# Ethernet_v2.net
KiCad netlist of a schematic drawn in Altium Designer
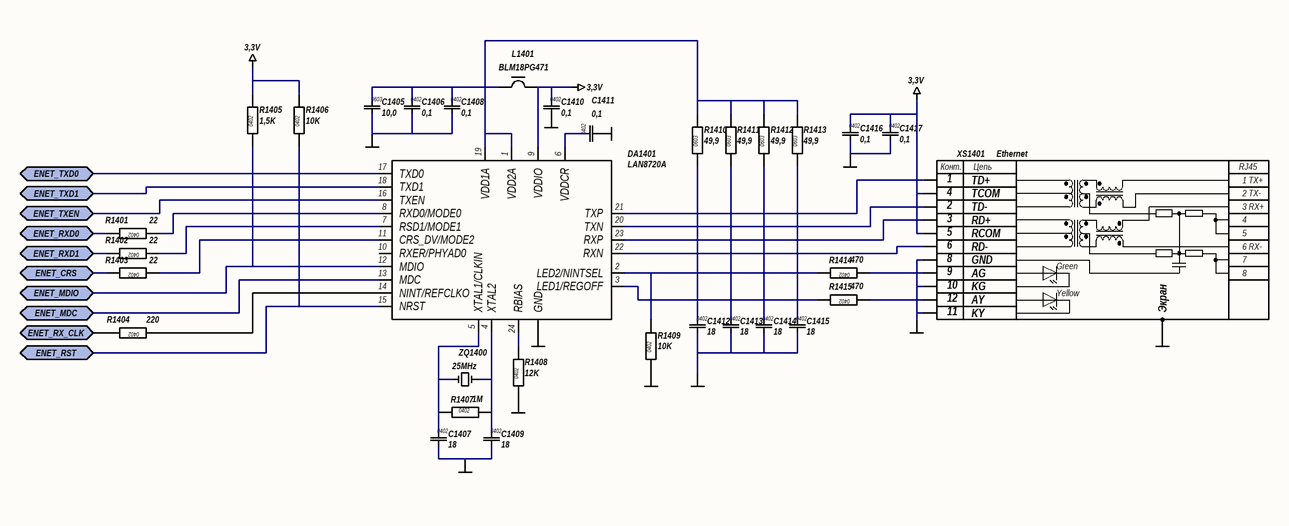
[diagram p0: Ethernet v2.SchDoc]

(export (version "E")
  (design (tool "Eeschema 10.0.6"))
  (components
    (comp (ref "C1405")
      (value "10,0")
      (footprint "CAP0603")
      (description "Конденсатор чип")
      (libsource (lib "EwgPassive") (part "CAP_0603"))
    )
    (comp (ref "C1406")
      (value "0,1")
      (footprint "CAP0402")
      (description "Конденсатор чип")
      (libsource (lib "EwgPassive") (part "CAP_0402"))
    )
    (comp (ref "C1407")
      (value "18")
      (footprint "CAP0402")
      (description "Конденсатор чип")
      (libsource (lib "EwgPassive") (part "CAP_0402"))
    )
    (comp (ref "C1408")
      (value "0,1")
      (footprint "CAP0402")
      (description "Конденсатор чип")
      (libsource (lib "EwgPassive") (part "CAP_0402"))
    )
    (comp (ref "C1409")
      (value "18")
      (footprint "CAP0402")
      (description "Конденсатор чип")
      (libsource (lib "EwgPassive") (part "CAP_0402"))
    )
    (comp (ref "C1410")
      (value "0,1")
      (footprint "CAP0402")
      (description "Конденсатор чип")
      (libsource (lib "EwgPassive") (part "CAP_0402"))
    )
    (comp (ref "C1411")
      (value "0,1")
      (footprint "CAP0402")
      (description "Конденсатор чип")
      (libsource (lib "EwgPassive") (part "CAP_0402"))
    )
    (comp (ref "C1412")
      (value "18")
      (footprint "CAP0402")
      (description "Конденсатор чип")
      (libsource (lib "EwgPassive") (part "CAP_0402"))
    )
    (comp (ref "C1413")
      (value "18")
      (footprint "CAP0402")
      (description "Конденсатор чип")
      (libsource (lib "EwgPassive") (part "CAP_0402"))
    )
    (comp (ref "C1414")
      (value "18")
      (footprint "CAP0402")
      (description "Конденсатор чип")
      (libsource (lib "EwgPassive") (part "CAP_0402"))
    )
    (comp (ref "C1415")
      (value "18")
      (footprint "CAP0402")
      (description "Конденсатор чип")
      (libsource (lib "EwgPassive") (part "CAP_0402"))
    )
    (comp (ref "C1416")
      (value "0,1")
      (footprint "CAP0402")
      (description "Конденсатор чип")
      (libsource (lib "EwgPassive") (part "CAP_0402"))
    )
    (comp (ref "C1417")
      (value "0,1")
      (footprint "CAP0402")
      (description "Конденсатор чип")
      (libsource (lib "EwgPassive") (part "CAP_0402"))
    )
    (comp (ref "DA1401")
      (value "LAN8720A")
      (footprint "LAN8720")
      (description "Интерфейс Ethernet")
      (libsource (lib "EwgMicrochips") (part "LAN8720A"))
    )
    (comp (ref "L1401")
      (value "BLM18PG471")
      (footprint "FB0603")
      (description "Ферритовая бусина")
      (libsource (lib "EwgPassive") (part "BLM18PG"))
    )
    (comp (ref "R1401")
      (value "22")
      (footprint "RES0402")
      (description "Резистор чип")
      (libsource (lib "EwgPassive") (part "RES_0402"))
    )
    (comp (ref "R1402")
      (value "22")
      (footprint "RES0402")
      (description "Резистор чип")
      (libsource (lib "EwgPassive") (part "RES_0402"))
    )
    (comp (ref "R1403")
      (value "22")
      (footprint "RES0402")
      (description "Резистор чип")
      (libsource (lib "EwgPassive") (part "RES_0402"))
    )
    (comp (ref "R1404")
      (value "220")
      (footprint "RES0402")
      (description "Резистор чип")
      (libsource (lib "EwgPassive") (part "RES_0402"))
    )
    (comp (ref "R1405")
      (value "1,5K")
      (footprint "RES0402")
      (description "Резистор чип")
      (libsource (lib "EwgPassive") (part "RES_0402"))
    )
    (comp (ref "R1406")
      (value "10K")
      (footprint "RES0402")
      (description "Резистор чип")
      (libsource (lib "EwgPassive") (part "RES_0402"))
    )
    (comp (ref "R1407")
      (value "1M")
      (footprint "RES0402")
      (description "Резистор чип")
      (libsource (lib "EwgPassive") (part "RES_0402"))
    )
    (comp (ref "R1408")
      (value "12K")
      (footprint "RES0402")
      (description "Резистор чип")
      (libsource (lib "") (part "RES_0402_1"))
    )
    (comp (ref "R1409")
      (value "10K")
      (footprint "RES0402")
      (description "Резистор чип")
      (libsource (lib "") (part "RES_0402_1"))
    )
    (comp (ref "R1410")
      (value "49,9")
      (footprint "RES0603")
      (description "Резистор чип")
      (libsource (lib "EwgPassive") (part "RES_0603"))
    )
    (comp (ref "R1411")
      (value "49,9")
      (footprint "RES0603")
      (description "Резистор чип")
      (libsource (lib "EwgPassive") (part "RES_0603"))
    )
    (comp (ref "R1412")
      (value "49,9")
      (footprint "RES0603")
      (description "Резистор чип")
      (libsource (lib "EwgPassive") (part "RES_0603"))
    )
    (comp (ref "R1413")
      (value "49,9")
      (footprint "RES0603")
      (description "Резистор чип")
      (libsource (lib "EwgPassive") (part "RES_0603"))
    )
    (comp (ref "R1414")
      (value "470")
      (footprint "RES0402")
      (description "Резистор чип")
      (libsource (lib "EwgPassive") (part "RES_0402"))
    )
    (comp (ref "R1415")
      (value "470")
      (footprint "RES0402")
      (description "Резистор чип")
      (libsource (lib "EwgPassive") (part "RES_0402"))
    )
    (comp (ref "XS1401")
      (value "Ethernet")
      (footprint "HR911105A")
      (description "Разъем RJ45 с трансформатором и LED")
      (libsource (lib "EwgConnectors") (part "RJ45-HR911105A"))
    )
    (comp (ref "ZQ1400")
      (value "25MHz")
      (footprint "KX-7")
      (description "Кварц")
      (libsource (lib "EwgPassive") (part "KX-7"))
    )
  )
  (nets
    (net (code "1") (name "/ENET_CRS") (class "Default") (node (ref "R1403") (pin "2") (pintype "passive")))
    (net (code "2") (name "/ENET_MDC") (class "Default")
      (node (ref "DA1401") (pin "13") (pinfunction "MDC_13") (pintype "passive"))
    )
    (net (code "3") (name "/ENET_MDIO") (class "Default")
      (node (ref "DA1401") (pin "12") (pinfunction "MDIO_12") (pintype "passive"))
      (node (ref "R1405") (pin "1") (pintype "passive"))
    )
    (net (code "4") (name "/ENET_RST") (class "Default")
      (node (ref "DA1401") (pin "15") (pinfunction "NRST_15") (pintype "passive"))
      (node (ref "R1406") (pin "1") (pintype "passive"))
    )
    (net (code "5") (name "/ENET_RXD0") (class "Default") (node (ref "R1401") (pin "2") (pintype "passive")))
    (net (code "6") (name "/ENET_RXD1") (class "Default") (node (ref "R1402") (pin "2") (pintype "passive")))
    (net (code "7") (name "/ENET_RX_CLK") (class "Default")
      (node (ref "R1404") (pin "2") (pintype "passive"))
    )
    (net (code "8") (name "/ENET_TXD0") (class "Default")
      (node (ref "DA1401") (pin "17") (pinfunction "TXD0_17") (pintype "passive"))
    )
    (net (code "9") (name "/ENET_TXD1") (class "Default")
      (node (ref "DA1401") (pin "18") (pinfunction "TXD1_18") (pintype "passive"))
    )
    (net (code "10") (name "/ENET_TXEN") (class "Default")
      (node (ref "DA1401") (pin "16") (pinfunction "TXEN_16") (pintype "passive"))
    )
    (net (code "11") (name "3,3V") (class "Default")
      (node (ref "C1410") (pin "1") (pintype "passive"))
      (node (ref "C1416") (pin "1") (pintype "passive"))
      (node (ref "C1417") (pin "1") (pintype "passive"))
      (node (ref "DA1401") (pin "9") (pinfunction "VDDIO_9") (pintype "passive"))
      (node (ref "L1401") (pin "2") (pintype "passive"))
      (node (ref "R1405") (pin "2") (pintype "passive"))
      (node (ref "R1406") (pin "2") (pintype "passive"))
      (node (ref "XS1401") (pin "4") (pinfunction "TCOM_4") (pintype "passive"))
      (node (ref "XS1401") (pin "5") (pinfunction "RCOM_5") (pintype "passive"))
    )
    (net (code "12") (name "GND") (class "Default")
      (node (ref "C1405") (pin "2") (pintype "passive"))
      (node (ref "C1406") (pin "2") (pintype "passive"))
      (node (ref "C1407") (pin "2") (pintype "passive"))
      (node (ref "C1408") (pin "2") (pintype "passive"))
      (node (ref "C1409") (pin "2") (pintype "passive"))
      (node (ref "C1410") (pin "2") (pintype "passive"))
      (node (ref "C1411") (pin "2") (pintype "passive"))
      (node (ref "C1412") (pin "2") (pintype "passive"))
      (node (ref "C1413") (pin "2") (pintype "passive"))
      (node (ref "C1414") (pin "2") (pintype "passive"))
      (node (ref "C1415") (pin "2") (pintype "passive"))
      (node (ref "C1416") (pin "2") (pintype "passive"))
      (node (ref "C1417") (pin "2") (pintype "passive"))
      (node (ref "DA1401") (pin "0") (pinfunction "GND_0") (pintype "passive"))
      (node (ref "R1408") (pin "1") (pintype "passive"))
      (node (ref "R1409") (pin "1") (pintype "passive"))
      (node (ref "XS1401") (pin "0") (pinfunction "Экран_0") (pintype "passive"))
      (node (ref "XS1401") (pin "10") (pinfunction "KG_10") (pintype "passive"))
      (node (ref "XS1401") (pin "11") (pinfunction "KY_11") (pintype "passive"))
      (node (ref "XS1401") (pin "8") (pinfunction "GND_8") (pintype "passive"))
    )
    (net (code "13") (name "Net-(DA1401-CRS_DV{slash}MODE2)") (class "Default")
      (node (ref "DA1401") (pin "11") (pinfunction "CRS_DV/MODE2_11") (pintype "passive"))
      (node (ref "R1403") (pin "1") (pintype "passive"))
    )
    (net (code "14") (name "Net-(DA1401-LED1{slash}REGOFF)") (class "Default")
      (node (ref "DA1401") (pin "3") (pinfunction "LED1/REGOFF_3") (pintype "passive"))
      (node (ref "R1415") (pin "2") (pintype "passive"))
    )
    (net (code "15") (name "Net-(DA1401-LED2{slash}NINTSEL)") (class "Default")
      (node (ref "DA1401") (pin "2") (pinfunction "LED2/NINTSEL_2") (pintype "passive"))
      (node (ref "R1409") (pin "2") (pintype "passive"))
      (node (ref "R1414") (pin "2") (pintype "passive"))
    )
    (net (code "16") (name "Net-(DA1401-NINT{slash}REFCLKO)") (class "Default")
      (node (ref "DA1401") (pin "14") (pinfunction "NINT/REFCLKO_14") (pintype "passive"))
      (node (ref "R1404") (pin "1") (pintype "passive"))
    )
    (net (code "17") (name "Net-(DA1401-RBIAS)") (class "Default")
      (node (ref "DA1401") (pin "24") (pinfunction "RBIAS_24") (pintype "passive"))
      (node (ref "R1408") (pin "2") (pintype "passive"))
    )
    (net (code "18") (name "Net-(DA1401-RSD1{slash}MODE1)") (class "Default")
      (node (ref "DA1401") (pin "7") (pinfunction "RSD1/MODE1_7") (pintype "passive"))
      (node (ref "R1402") (pin "1") (pintype "passive"))
    )
    (net (code "19") (name "Net-(DA1401-RXD0{slash}MODE0)") (class "Default")
      (node (ref "DA1401") (pin "8") (pinfunction "RXD0/MODE0_8") (pintype "passive"))
      (node (ref "R1401") (pin "1") (pintype "passive"))
    )
    (net (code "20") (name "Net-(DA1401-RXN)") (class "Default")
      (node (ref "C1415") (pin "1") (pintype "passive"))
      (node (ref "DA1401") (pin "22") (pinfunction "RXN_22") (pintype "passive"))
      (node (ref "R1413") (pin "1") (pintype "passive"))
      (node (ref "XS1401") (pin "6") (pinfunction "RD-_6") (pintype "passive"))
    )
    (net (code "21") (name "Net-(DA1401-RXP)") (class "Default")
      (node (ref "C1414") (pin "1") (pintype "passive"))
      (node (ref "DA1401") (pin "23") (pinfunction "RXP_23") (pintype "passive"))
      (node (ref "R1412") (pin "1") (pintype "passive"))
      (node (ref "XS1401") (pin "3") (pinfunction "RD+_3") (pintype "passive"))
    )
    (net (code "22") (name "Net-(DA1401-TXN)") (class "Default")
      (node (ref "C1413") (pin "1") (pintype "passive"))
      (node (ref "DA1401") (pin "20") (pinfunction "TXN_20") (pintype "passive"))
      (node (ref "R1411") (pin "1") (pintype "passive"))
      (node (ref "XS1401") (pin "2") (pinfunction "TD-_2") (pintype "passive"))
    )
    (net (code "23") (name "Net-(DA1401-TXP)") (class "Default")
      (node (ref "C1412") (pin "1") (pintype "passive"))
      (node (ref "DA1401") (pin "21") (pinfunction "TXP_21") (pintype "passive"))
      (node (ref "R1410") (pin "1") (pintype "passive"))
      (node (ref "XS1401") (pin "1") (pinfunction "TD+_1") (pintype "passive"))
    )
    (net (code "24") (name "Net-(DA1401-VDD1A)") (class "Default")
      (node (ref "C1405") (pin "1") (pintype "passive"))
      (node (ref "C1406") (pin "1") (pintype "passive"))
      (node (ref "C1408") (pin "1") (pintype "passive"))
      (node (ref "DA1401") (pin "1") (pinfunction "VDD2A_1") (pintype "passive"))
      (node (ref "DA1401") (pin "19") (pinfunction "VDD1A_19") (pintype "passive"))
      (node (ref "L1401") (pin "1") (pintype "passive"))
      (node (ref "R1410") (pin "2") (pintype "passive"))
      (node (ref "R1411") (pin "2") (pintype "passive"))
      (node (ref "R1412") (pin "2") (pintype "passive"))
      (node (ref "R1413") (pin "2") (pintype "passive"))
    )
    (net (code "25") (name "Net-(DA1401-VDDCR)") (class "Default")
      (node (ref "C1411") (pin "1") (pintype "passive"))
      (node (ref "DA1401") (pin "6") (pinfunction "VDDCR_6") (pintype "passive"))
    )
    (net (code "26") (name "Net-(DA1401-XTAL1{slash}CLKIN)") (class "Default")
      (node (ref "C1407") (pin "1") (pintype "passive"))
      (node (ref "DA1401") (pin "5") (pinfunction "XTAL1/CLKIN_5") (pintype "passive"))
      (node (ref "R1407") (pin "1") (pintype "passive"))
      (node (ref "ZQ1400") (pin "1") (pintype "passive"))
    )
    (net (code "27") (name "Net-(DA1401-XTAL2)") (class "Default")
      (node (ref "C1409") (pin "1") (pintype "passive"))
      (node (ref "DA1401") (pin "4") (pinfunction "XTAL2_4") (pintype "passive"))
      (node (ref "R1407") (pin "2") (pintype "passive"))
      (node (ref "ZQ1400") (pin "3") (pintype "passive"))
    )
    (net (code "28") (name "Net-(XS1401-AG)") (class "Default")
      (node (ref "R1414") (pin "1") (pintype "passive"))
      (node (ref "XS1401") (pin "9") (pinfunction "AG_9") (pintype "passive"))
    )
    (net (code "29") (name "Net-(XS1401-AY)") (class "Default")
      (node (ref "R1415") (pin "1") (pintype "passive"))
      (node (ref "XS1401") (pin "12") (pinfunction "AY_12") (pintype "passive"))
    )
    (net (code "30") (name "unconnected-(DA1401-RXER{slash}PHYAD0-Pad10)") (class "Default")
      (node (ref "DA1401") (pin "10") (pinfunction "RXER/PHYAD0_10") (pintype "passive"))
    )
    (net (code "31") (name "unconnected-(ZQ1400-Pad2)") (class "Default")
      (node (ref "ZQ1400") (pin "2") (pintype "passive"))
    )
    (net (code "32") (name "unconnected-(ZQ1400-Pad4)") (class "Default")
      (node (ref "ZQ1400") (pin "4") (pintype "passive"))
    )
  )
)
